# Sheet1.net
KiCad netlist of a schematic drawn in Altium Designer
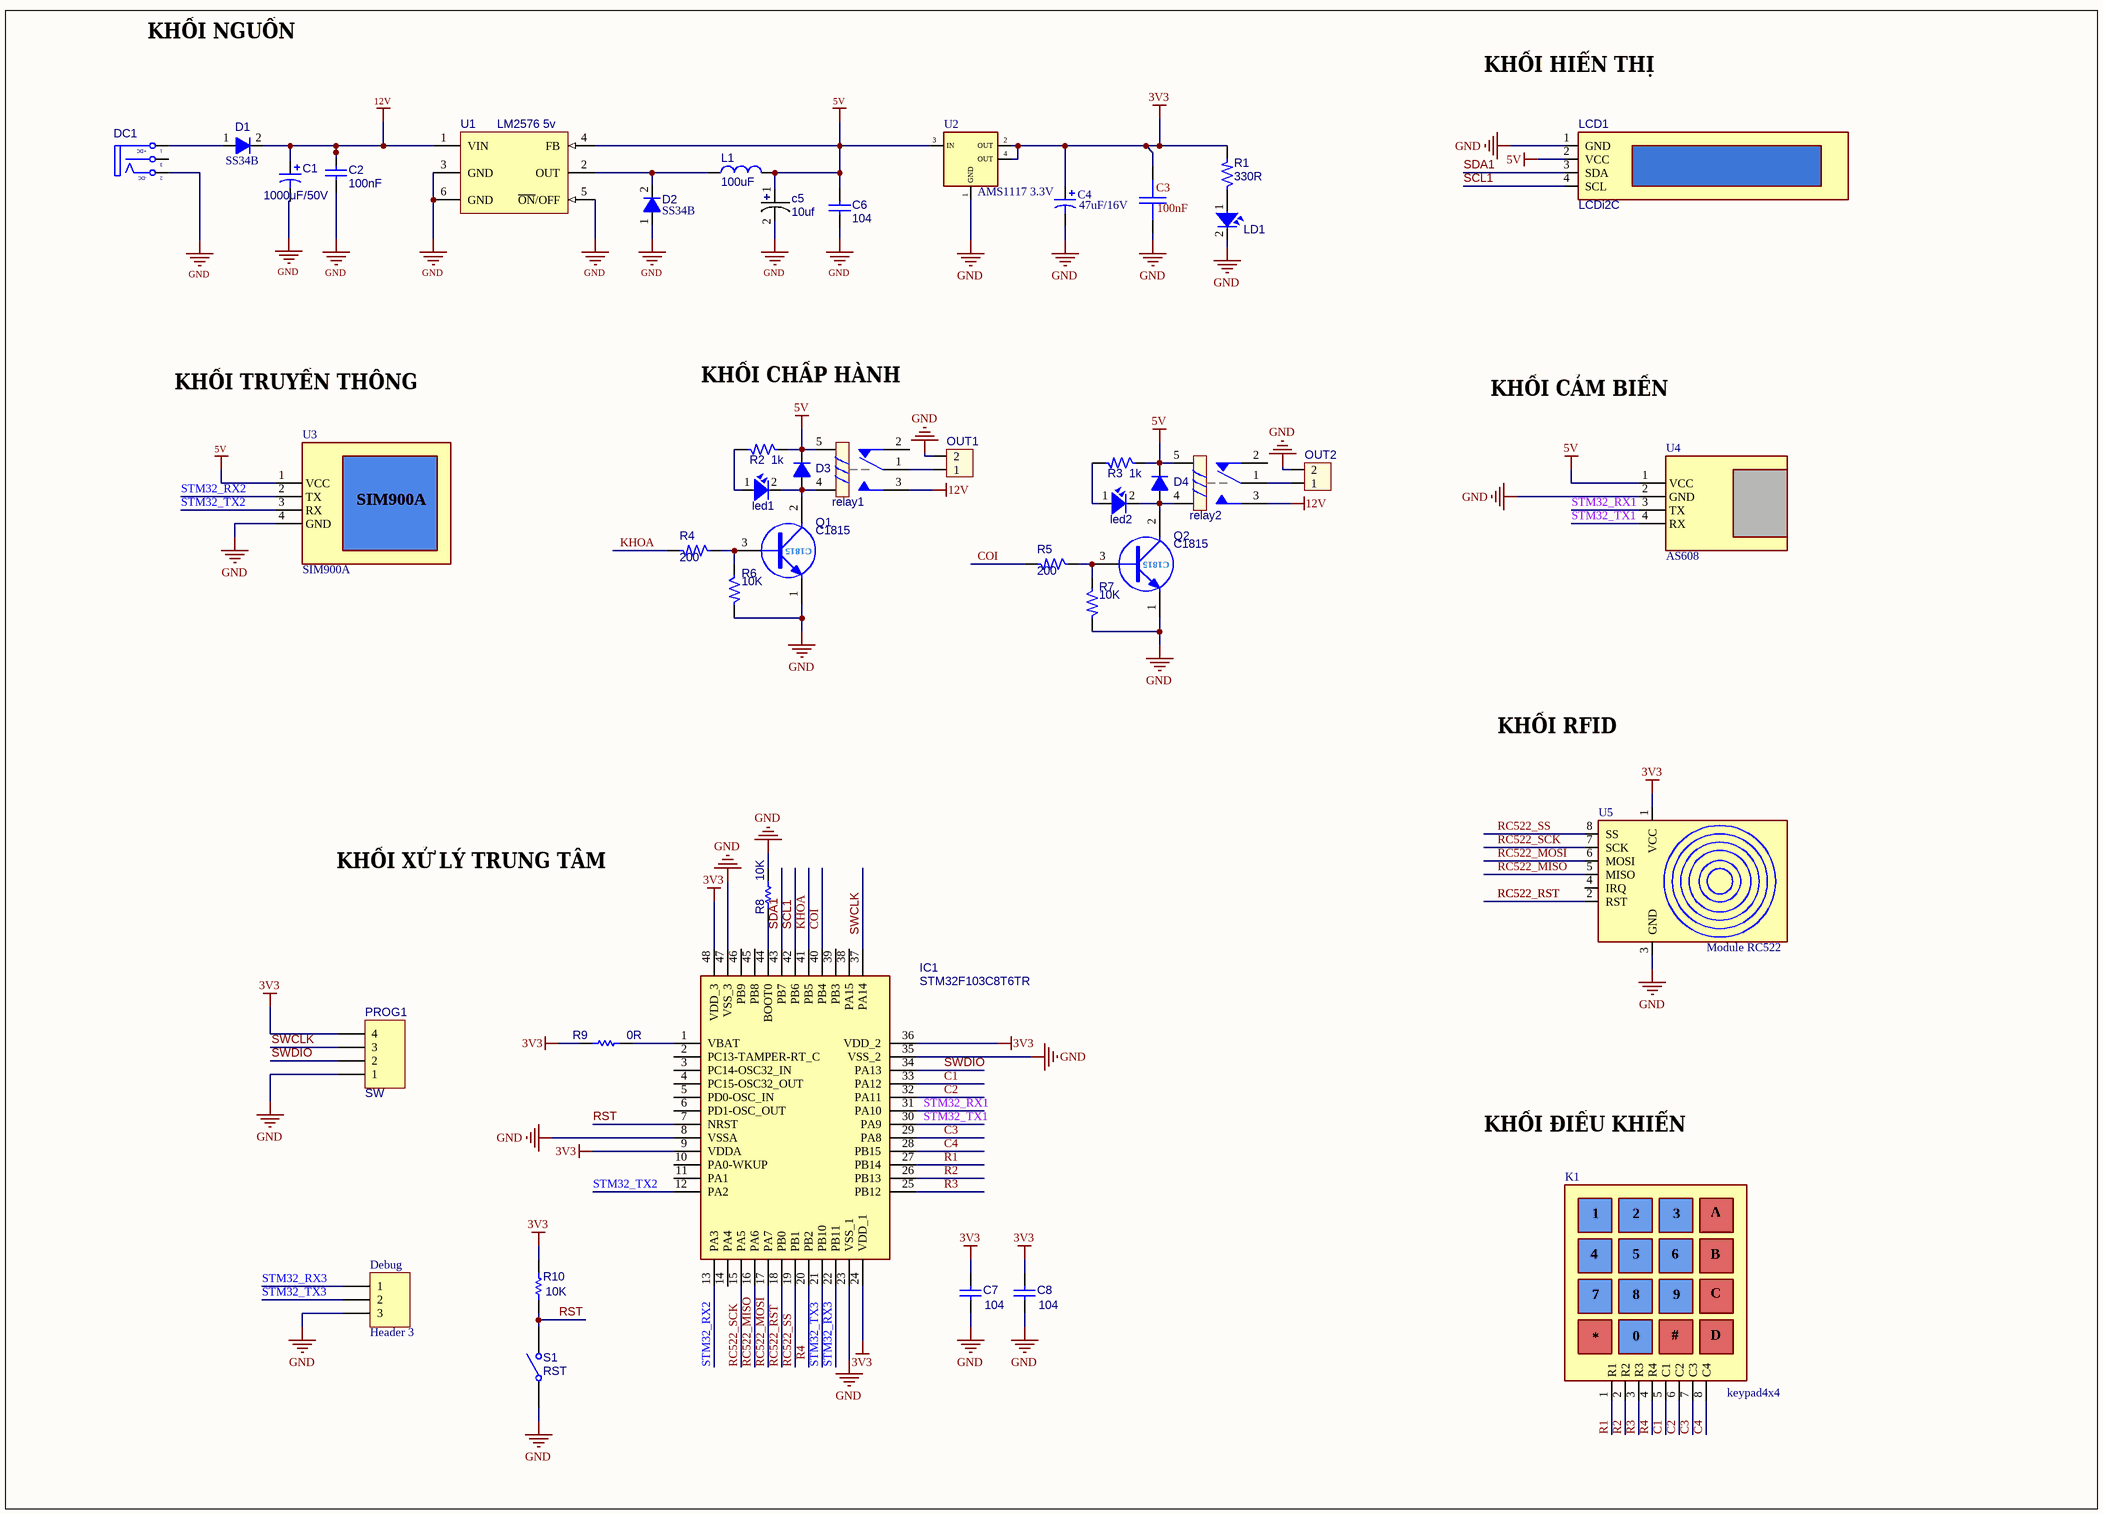
[diagram p0: Sheet1.SchDoc]

(export (version "E")
  (design (tool "Eeschema 10.0.6"))
  (components
    (comp (ref "C1")
      (value "1000uF/50V")
      (footprint "C_EL_10_12")
      (description "Polarized Capacitor (Radial)")
      (fields (field (name "Comment") "1000uF-50V-DIP") (field (name "PUBLISHER") "Altium Limited"))
      (libsource (lib "Miscellaneous Devices") (part "Cap Pol1"))
    )
    (comp (ref "C2")
      (value "100nF")
      (footprint "C0805S")
      (description "Capacitor")
      (fields (field (name "Comment") "100nF-50V-126") (field (name "PUBLISHER") "Altium Limited"))
      (libsource (lib "Miscellaneous Devices") (part "Cap"))
    )
    (comp (ref "C3")
      (value "100nF")
      (footprint "C0805S")
      (description "Capacitor, Ceramic Chip, 16V, X7R, 10%")
      (fields
        (field (name "MANUFACTURER") "Samsung Electromechanics")
        (field (name "PARTNUMBER") "CL05B104KO5NNNC")
      )
      (libsource (lib "PADSlegacy_Passive") (part "C0402"))
    )
    (comp (ref "C4")
      (value "47uF/16V")
      (footprint "6032")
      (description "Polarized Capacitor (Radial)")
      (fields (field (name "Comment") "Tanta-47uF-16V-2917") (field (name "PUBLISHER") "Altium Limited"))
      (libsource (lib "Miscellaneous Devices") (part "Cap Pol1"))
    )
    (comp (ref "c5")
      (value "10uf")
      (footprint "C_EL_10_9")
      (libsource (lib "Schlib_do_an_2019") (part "radial"))
    )
    (comp (ref "C6")
      (value "104")
      (footprint "C0805S")
      (description "Capacitor (Semiconductor SIM Model)")
      (fields (field (name "PUBLISHER") "Altium Limited"))
      (libsource (lib "Pcblib_do_an_2019") (part "Cap 104_SMD"))
    )
    (comp (ref "C7")
      (value "104")
      (footprint "C0805S")
      (description "Capacitor")
      (fields (field (name "Comment") "Cap") (field (name "PUBLISHER") "Altium Limited"))
      (libsource (lib "Miscellaneous Devices") (part "Cap"))
    )
    (comp (ref "C8")
      (value "104")
      (footprint "C0805S")
      (description "Capacitor")
      (fields (field (name "Comment") "Cap") (field (name "PUBLISHER") "Altium Limited"))
      (libsource (lib "Miscellaneous Devices") (part "Cap"))
    )
    (comp (ref "D1") (value "SS34B") (footprint "D_SMB") (libsource (lib "Schlib_do_an_2019") (part "diode")))
    (comp (ref "D2") (value "SS34B") (footprint "D_SMB") (libsource (lib "Schlib_do_an_2019") (part "diode")))
    (comp (ref "D3") (value "diode") (footprint "D_SMA") (libsource (lib "Pcblib_do_an_2019") (part "diode")))
    (comp (ref "D4") (value "diode") (footprint "D_SMA") (libsource (lib "Pcblib_do_an_2019") (part "diode")))
    (comp (ref "DC1")
      (value "Jack DC5.5x2.5MM DC5525")
      (footprint "DC-IN")
      (description "Jac DC input")
      (libsource (lib "syhaunguyen") (part "DCIN"))
    )
    (comp (ref "Debug")
      (value "Header 3")
      (footprint "XH_3")
      (description "Header, 3-Pin")
      (fields (field (name "PUBLISHER") "Altium Limited"))
      (libsource (lib "Miscellaneous Connectors") (part "Header 3"))
    )
    (comp (ref "IC1")
      (value "STM32F103C8T6TR")
      (footprint "QFN48N")
      (description "Integrated Circuit")
      (fields (field (name "MOUSER PART NUMBER") "511-STM32F103C8T6TR"))
      (libsource (lib "*") (part "STM32F103C8T6TR"))
    )
    (comp (ref "K1") (value "keypad4x4") (footprint "XH_8") (libsource (lib "kctm_lib") (part "keypad")))
    (comp (ref "L1")
      (value "100uF")
      (footprint "L_12")
      (description "Inductor")
      (libsource (lib "Lib_Chuan_03_08_2013") (part "L1"))
    )
    (comp (ref "LCD1") (value "LCDi2C") (footprint "XH_4") (libsource (lib "lib_vuon_dua") (part "LCDi2C")))
    (comp (ref "LD1")
      (value "led 0805 green")
      (footprint "LED0805GRN")
      (libsource (lib "Schlib_do_an_2019") (part "led"))
    )
    (comp (ref "led1")
      (value "led")
      (footprint "led 5mm red dip")
      (libsource (lib "Schlib_do_an_2019") (part "led"))
    )
    (comp (ref "led2")
      (value "led")
      (footprint "led 5mm red dip")
      (libsource (lib "Schlib_do_an_2019") (part "led"))
    )
    (comp (ref "OUT1")
      (value "con2")
      (footprint "MSTBF_2")
      (libsource (lib "Schlib_do_an_2019") (part "con2"))
    )
    (comp (ref "OUT2")
      (value "con2")
      (footprint "MSTBF_2")
      (libsource (lib "Schlib_do_an_2019") (part "con2"))
    )
    (comp (ref "PROG1")
      (value "SW")
      (footprint "XH_4")
      (description "Header, 4-Pin")
      (fields (field (name "PUBLISHER") "Altium Limited"))
      (libsource (lib "Miscellaneous Connectors") (part "Header 4"))
    )
    (comp (ref "Q1")
      (value "C1815")
      (footprint "VuNgocDang:TO-92W")
      (libsource (lib "Schlib_do_an_2019") (part "C1815"))
    )
    (comp (ref "Q2")
      (value "C1815")
      (footprint "VuNgocDang:TO-92W")
      (libsource (lib "Schlib_do_an_2019") (part "C1815"))
    )
    (comp (ref "R1")
      (value "330R")
      (footprint "R0805E")
      (description "Resistor 1/4W")
      (libsource (lib "library_2") (part "R"))
    )
    (comp (ref "R2")
      (value "1k")
      (footprint "R0805E")
      (description "Resistor 1/4W")
      (libsource (lib "Pcblib_do_an_2019") (part "R"))
    )
    (comp (ref "R3")
      (value "1k")
      (footprint "R0805E")
      (description "Resistor 1/4W")
      (libsource (lib "Pcblib_do_an_2019") (part "R"))
    )
    (comp (ref "R4")
      (value "200")
      (footprint "R0125W_AX03")
      (description "Resistor 1/4W")
      (libsource (lib "Pcblib_do_an_2019") (part "R"))
    )
    (comp (ref "R5")
      (value "200")
      (footprint "R0125W_AX03")
      (description "Resistor 1/4W")
      (libsource (lib "Pcblib_do_an_2019") (part "R"))
    )
    (comp (ref "R6")
      (value "10K")
      (footprint "R0805E")
      (description "Resistor 1/4W")
      (libsource (lib "Pcblib_do_an_2019") (part "R"))
    )
    (comp (ref "R7")
      (value "10K")
      (footprint "R0805E")
      (description "Resistor 1/4W")
      (libsource (lib "Pcblib_do_an_2019") (part "R"))
    )
    (comp (ref "R8")
      (value "10K")
      (footprint "SmartDoor:R0805E")
      (description "Resistor")
      (fields (field (name "Comment") "Res1") (field (name "PUBLISHER") "Altium Limited"))
      (libsource (lib "Miscellaneous Devices") (part "Res1"))
    )
    (comp (ref "R9")
      (value "0R")
      (footprint "R0805S")
      (description "Resistor")
      (fields (field (name "Comment") "Res1") (field (name "PUBLISHER") "Altium Limited"))
      (libsource (lib "Miscellaneous Devices") (part "Res1"))
    )
    (comp (ref "R10")
      (value "10K")
      (footprint "R0805S")
      (description "Resistor")
      (fields (field (name "Comment") "Res1") (field (name "PUBLISHER") "Altium Limited"))
      (libsource (lib "Miscellaneous Devices") (part "Res1"))
    )
    (comp (ref "relay1")
      (value "relay2")
      (footprint "RL_SPDT_10A")
      (libsource (lib "Schlib_do_an_2019") (part "relay2"))
    )
    (comp (ref "relay2")
      (value "relay2")
      (footprint "RL_SPDT_10A")
      (libsource (lib "Schlib_do_an_2019") (part "relay2"))
    )
    (comp (ref "S1")
      (value "RST")
      (footprint "SW1-SMD")
      (description "Single-Pole, Single-Throw Switch")
      (fields (field (name "PUBLISHER") "Altium Limited"))
      (libsource (lib "Miscellaneous Devices") (part "SW-SPST"))
    )
    (comp (ref "U1")
      (value "LM2576 5v")
      (footprint "TO-263-5L, D2PAK-5, DDPAK, FMG170_5_S1000")
      (description "SIMPLE SWITCHER; 3A Step-Down Voltage Regulator")
      (fields
        (field (name "PARTNUMBER") "LM2576T-5.0")
        (field (name "MANUFACTURER") "National Semiconductor")
        (field (name "PUBLISHER") "Altium Limited")
      )
      (libsource (lib "Lib_Chuan_03_08_2013") (part "LM2576T-5.0"))
    )
    (comp (ref "U2")
      (value "AMS1117 3.3V")
      (footprint "TranVanDen:ASM1117-3V3")
      (libsource (lib "HF6200_Lib") (part "AMS1117"))
    )
    (comp (ref "U3") (value "SIM900A") (footprint "XH_4") (libsource (lib "SmartDoor") (part "SIM900A")))
    (comp (ref "U4") (value "AS608") (footprint "XH_4") (libsource (lib "user_lib") (part "R307")))
    (comp (ref "U5")
      (value "Module RC522")
      (footprint "XH_8")
      (libsource (lib "QuanLyHangHoa_Lib") (part "Module RC522"))
    )
  )
  (nets
    (net (code "1") (name "/C1") (class "Default")
      (node (ref "IC1") (pin "33") (pinfunction "PA12_33") (pintype "passive"))
      (node (ref "K1") (pin "5") (pinfunction "C1_5") (pintype "passive"))
    )
    (net (code "2") (name "/C2") (class "Default")
      (node (ref "IC1") (pin "32") (pinfunction "PA11_32") (pintype "passive"))
      (node (ref "K1") (pin "6") (pinfunction "C2_6") (pintype "passive"))
    )
    (net (code "3") (name "/C3") (class "Default")
      (node (ref "IC1") (pin "29") (pinfunction "PA8_29") (pintype "passive"))
      (node (ref "K1") (pin "7") (pinfunction "C3_7") (pintype "passive"))
    )
    (net (code "4") (name "/C4") (class "Default")
      (node (ref "IC1") (pin "28") (pinfunction "PB15_28") (pintype "passive"))
      (node (ref "K1") (pin "8") (pinfunction "C4_8") (pintype "passive"))
    )
    (net (code "5") (name "/COI") (class "Default")
      (node (ref "IC1") (pin "40") (pinfunction "PB4_40") (pintype "passive"))
      (node (ref "R5") (pin "2") (pinfunction "2_2") (pintype "passive"))
    )
    (net (code "6") (name "/KHOA") (class "Default")
      (node (ref "IC1") (pin "41") (pinfunction "PB5_41") (pintype "passive"))
      (node (ref "R4") (pin "2") (pinfunction "2_2") (pintype "passive"))
    )
    (net (code "7") (name "/R1") (class "Default")
      (node (ref "IC1") (pin "27") (pinfunction "PB14_27") (pintype "passive"))
      (node (ref "K1") (pin "1") (pinfunction "R1_1") (pintype "passive"))
    )
    (net (code "8") (name "/R2") (class "Default")
      (node (ref "IC1") (pin "26") (pinfunction "PB13_26") (pintype "passive"))
      (node (ref "K1") (pin "2") (pinfunction "R2_2") (pintype "passive"))
    )
    (net (code "9") (name "/R3") (class "Default")
      (node (ref "IC1") (pin "25") (pinfunction "PB12_25") (pintype "passive"))
      (node (ref "K1") (pin "3") (pinfunction "R3_3") (pintype "passive"))
    )
    (net (code "10") (name "/R4") (class "Default")
      (node (ref "IC1") (pin "20") (pinfunction "PB2_20") (pintype "passive"))
      (node (ref "K1") (pin "4") (pinfunction "R4_4") (pintype "passive"))
    )
    (net (code "11") (name "/RC522_MISO") (class "Default")
      (node (ref "IC1") (pin "16") (pinfunction "PA6_16") (pintype "passive"))
      (node (ref "U5") (pin "5") (pinfunction "MISO_5") (pintype "passive"))
    )
    (net (code "12") (name "/RC522_MOSI") (class "Default")
      (node (ref "IC1") (pin "17") (pinfunction "PA7_17") (pintype "passive"))
      (node (ref "U5") (pin "6") (pinfunction "MOSI_6") (pintype "passive"))
    )
    (net (code "13") (name "/RC522_RST") (class "Default")
      (node (ref "IC1") (pin "18") (pinfunction "PB0_18") (pintype "passive"))
      (node (ref "U5") (pin "2") (pinfunction "RST_2") (pintype "passive"))
    )
    (net (code "14") (name "/RC522_SCK") (class "Default")
      (node (ref "IC1") (pin "15") (pinfunction "PA5_15") (pintype "passive"))
      (node (ref "U5") (pin "7") (pinfunction "SCK_7") (pintype "passive"))
    )
    (net (code "15") (name "/RC522_SS") (class "Default")
      (node (ref "IC1") (pin "19") (pinfunction "PB1_19") (pintype "passive"))
      (node (ref "U5") (pin "8") (pinfunction "SS_8") (pintype "passive"))
    )
    (net (code "16") (name "/RST") (class "Default")
      (node (ref "IC1") (pin "7") (pinfunction "NRST_7") (pintype "passive"))
      (node (ref "R10") (pin "1") (pinfunction "1_1") (pintype "passive"))
      (node (ref "S1") (pin "2") (pinfunction "NO_2") (pintype "passive"))
    )
    (net (code "17") (name "/SCL1") (class "Default")
      (node (ref "IC1") (pin "42") (pinfunction "PB6_42") (pintype "passive"))
      (node (ref "LCD1") (pin "4") (pinfunction "SCL_4") (pintype "passive"))
    )
    (net (code "18") (name "/SDA1") (class "Default")
      (node (ref "IC1") (pin "43") (pinfunction "PB7_43") (pintype "passive"))
      (node (ref "LCD1") (pin "3") (pinfunction "SDA_3") (pintype "passive"))
    )
    (net (code "19") (name "/STM32_RX1") (class "Default")
      (node (ref "IC1") (pin "31") (pinfunction "PA10_31") (pintype "passive"))
      (node (ref "U4") (pin "3") (pinfunction "TX_3") (pintype "passive"))
    )
    (net (code "20") (name "/STM32_RX2") (class "Default")
      (node (ref "IC1") (pin "13") (pinfunction "PA3_13") (pintype "passive"))
      (node (ref "U3") (pin "2") (pinfunction "TX_2") (pintype "passive"))
    )
    (net (code "21") (name "/STM32_RX3") (class "Default")
      (node (ref "Debug") (pin "1") (pinfunction "1_1") (pintype "passive"))
      (node (ref "IC1") (pin "22") (pinfunction "PB11_22") (pintype "passive"))
    )
    (net (code "22") (name "/STM32_TX1") (class "Default")
      (node (ref "IC1") (pin "30") (pinfunction "PA9_30") (pintype "passive"))
      (node (ref "U4") (pin "4") (pinfunction "RX_4") (pintype "passive"))
    )
    (net (code "23") (name "/STM32_TX2") (class "Default")
      (node (ref "IC1") (pin "12") (pinfunction "PA2_12") (pintype "passive"))
      (node (ref "U3") (pin "3") (pinfunction "RX_3") (pintype "passive"))
    )
    (net (code "24") (name "/STM32_TX3") (class "Default")
      (node (ref "Debug") (pin "2") (pinfunction "2_2") (pintype "passive"))
      (node (ref "IC1") (pin "21") (pinfunction "PB10_21") (pintype "passive"))
    )
    (net (code "25") (name "/SWCLK") (class "Default")
      (node (ref "IC1") (pin "37") (pinfunction "PA14_37") (pintype "passive"))
      (node (ref "PROG1") (pin "3") (pinfunction "3_3") (pintype "passive"))
    )
    (net (code "26") (name "/SWDIO") (class "Default")
      (node (ref "IC1") (pin "34") (pinfunction "PA13_34") (pintype "passive"))
      (node (ref "PROG1") (pin "2") (pinfunction "2_2") (pintype "passive"))
    )
    (net (code "27") (name "3V3") (class "Default")
      (node (ref "C3") (pin "2") (pinfunction "2_2") (pintype "passive"))
      (node (ref "C4") (pin "1") (pinfunction "1_1") (pintype "passive"))
      (node (ref "C7") (pin "2") (pinfunction "2_2") (pintype "passive"))
      (node (ref "C8") (pin "2") (pinfunction "2_2") (pintype "passive"))
      (node (ref "IC1") (pin "24") (pinfunction "VDD_1_24") (pintype "passive"))
      (node (ref "IC1") (pin "36") (pinfunction "VDD_2_36") (pintype "passive"))
      (node (ref "IC1") (pin "48") (pinfunction "VDD_3_48") (pintype "passive"))
      (node (ref "IC1") (pin "9") (pinfunction "VDDA_9") (pintype "passive"))
      (node (ref "PROG1") (pin "4") (pinfunction "4_4") (pintype "passive"))
      (node (ref "R1") (pin "2") (pinfunction "2_2") (pintype "passive"))
      (node (ref "R10") (pin "2") (pinfunction "2_2") (pintype "passive"))
      (node (ref "R9") (pin "2") (pinfunction "2_2") (pintype "passive"))
      (node (ref "U2") (pin "2") (pinfunction "OUT_2") (pintype "passive"))
      (node (ref "U2") (pin "4") (pinfunction "OUT_4") (pintype "passive"))
      (node (ref "U5") (pin "1") (pinfunction "VCC_1") (pintype "passive"))
    )
    (net (code "28") (name "5V") (class "Default")
      (node (ref "C6") (pin "2") (pintype "passive"))
      (node (ref "D3") (pin "2") (pinfunction "K_2") (pintype "passive"))
      (node (ref "D4") (pin "2") (pinfunction "K_2") (pintype "passive"))
      (node (ref "L1") (pin "2") (pinfunction "2_2") (pintype "passive"))
      (node (ref "LCD1") (pin "2") (pinfunction "VCC_2") (pintype "passive"))
      (node (ref "R2") (pin "1") (pinfunction "1_1") (pintype "passive"))
      (node (ref "R3") (pin "1") (pinfunction "1_1") (pintype "passive"))
      (node (ref "U1") (pin "4") (pinfunction "FB_4") (pintype "input"))
      (node (ref "U2") (pin "3") (pinfunction "IN_3") (pintype "passive"))
      (node (ref "U3") (pin "1") (pinfunction "VCC_1") (pintype "passive"))
      (node (ref "U4") (pin "1") (pinfunction "VCC_1") (pintype "passive"))
      (node (ref "c5") (pin "1") (pinfunction "1_1") (pintype "passive"))
      (node (ref "relay1") (pin "5") (pinfunction "5_5") (pintype "passive"))
      (node (ref "relay2") (pin "5") (pinfunction "5_5") (pintype "passive"))
    )
    (net (code "29") (name "12V") (class "Default")
      (node (ref "C1") (pin "1") (pinfunction "1_1") (pintype "passive"))
      (node (ref "C2") (pin "1") (pinfunction "1_1") (pintype "passive"))
      (node (ref "D1") (pin "2") (pinfunction "K_2") (pintype "passive"))
      (node (ref "U1") (pin "1") (pinfunction "VIN_1") (pintype "power_in"))
      (node (ref "relay1") (pin "3") (pinfunction "3_3") (pintype "passive"))
      (node (ref "relay2") (pin "3") (pinfunction "3_3") (pintype "passive"))
    )
    (net (code "30") (name "GND") (class "Default")
      (node (ref "C1") (pin "2") (pinfunction "2_2") (pintype "passive"))
      (node (ref "C2") (pin "2") (pinfunction "2_2") (pintype "passive"))
      (node (ref "C3") (pin "1") (pinfunction "1_1") (pintype "passive"))
      (node (ref "C4") (pin "2") (pinfunction "2_2") (pintype "passive"))
      (node (ref "C6") (pin "1") (pintype "passive"))
      (node (ref "C7") (pin "1") (pinfunction "1_1") (pintype "passive"))
      (node (ref "C8") (pin "1") (pinfunction "1_1") (pintype "passive"))
      (node (ref "D2") (pin "1") (pinfunction "A_1") (pintype "passive"))
      (node (ref "DC1") (pin "2") (pinfunction "TN_2") (pintype "passive"))
      (node (ref "Debug") (pin "3") (pinfunction "3_3") (pintype "passive"))
      (node (ref "IC1") (pin "23") (pinfunction "VSS_1_23") (pintype "passive"))
      (node (ref "IC1") (pin "35") (pinfunction "VSS_2_35") (pintype "passive"))
      (node (ref "IC1") (pin "47") (pinfunction "VSS_3_47") (pintype "passive"))
      (node (ref "IC1") (pin "8") (pinfunction "VSSA_8") (pintype "passive"))
      (node (ref "LCD1") (pin "1") (pinfunction "GND_1") (pintype "passive"))
      (node (ref "LD1") (pin "2") (pinfunction "1_2") (pintype "passive"))
      (node (ref "OUT1") (pin "2") (pinfunction "2_2") (pintype "passive"))
      (node (ref "OUT2") (pin "2") (pinfunction "2_2") (pintype "passive"))
      (node (ref "PROG1") (pin "1") (pinfunction "1_1") (pintype "passive"))
      (node (ref "Q1") (pin "1") (pinfunction "E_1") (pintype "passive"))
      (node (ref "Q2") (pin "1") (pinfunction "E_1") (pintype "passive"))
      (node (ref "R6") (pin "2") (pinfunction "2_2") (pintype "passive"))
      (node (ref "R7") (pin "2") (pinfunction "2_2") (pintype "passive"))
      (node (ref "R8") (pin "1") (pinfunction "1_1") (pintype "passive"))
      (node (ref "S1") (pin "1") (pinfunction "COMMON_1") (pintype "passive"))
      (node (ref "U1") (pin "3") (pinfunction "GND_3") (pintype "power_in"))
      (node (ref "U1") (pin "5") (pinfunction "~{ON}/OFF_5") (pintype "input"))
      (node (ref "U1") (pin "6") (pinfunction "GND_6") (pintype "passive"))
      (node (ref "U2") (pin "1") (pinfunction "GND_1") (pintype "passive"))
      (node (ref "U3") (pin "4") (pinfunction "GND_4") (pintype "passive"))
      (node (ref "U4") (pin "2") (pinfunction "GND_2") (pintype "passive"))
      (node (ref "U5") (pin "3") (pinfunction "GND_3") (pintype "passive"))
      (node (ref "c5") (pin "2") (pinfunction "2_2") (pintype "passive"))
    )
    (net (code "31") (name "Net-(D1-A)") (class "Default")
      (node (ref "D1") (pin "1") (pinfunction "A_1") (pintype "passive"))
      (node (ref "DC1") (pin "1") (pinfunction "T_1") (pintype "passive"))
    )
    (net (code "32") (name "Net-(D2-K)") (class "Default")
      (node (ref "D2") (pin "2") (pinfunction "K_2") (pintype "passive"))
      (node (ref "L1") (pin "1") (pinfunction "1_1") (pintype "passive"))
      (node (ref "U1") (pin "2") (pinfunction "OUT_2") (pintype "power_in"))
    )
    (net (code "33") (name "Net-(D3-A)") (class "Default")
      (node (ref "D3") (pin "1") (pinfunction "A_1") (pintype "passive"))
      (node (ref "Q1") (pin "2") (pinfunction "C_2") (pintype "passive"))
      (node (ref "led1") (pin "2") (pinfunction "1_2") (pintype "passive"))
      (node (ref "relay1") (pin "4") (pinfunction "4_4") (pintype "passive"))
    )
    (net (code "34") (name "Net-(D4-A)") (class "Default")
      (node (ref "D4") (pin "1") (pinfunction "A_1") (pintype "passive"))
      (node (ref "Q2") (pin "2") (pinfunction "C_2") (pintype "passive"))
      (node (ref "led2") (pin "2") (pinfunction "1_2") (pintype "passive"))
      (node (ref "relay2") (pin "4") (pinfunction "4_4") (pintype "passive"))
    )
    (net (code "35") (name "Net-(IC1-BOOT0)") (class "Default")
      (node (ref "IC1") (pin "44") (pinfunction "BOOT0_44") (pintype "passive"))
      (node (ref "R8") (pin "2") (pinfunction "2_2") (pintype "passive"))
    )
    (net (code "36") (name "Net-(IC1-VBAT)") (class "Default")
      (node (ref "IC1") (pin "1") (pinfunction "VBAT_1") (pintype "passive"))
      (node (ref "R9") (pin "1") (pinfunction "1_1") (pintype "passive"))
    )
    (net (code "37") (name "Net-(LD1-A)") (class "Default")
      (node (ref "LD1") (pin "1") (pinfunction "A_1") (pintype "passive"))
      (node (ref "R1") (pin "1") (pinfunction "1_1") (pintype "passive"))
    )
    (net (code "38") (name "Net-(OUT1-Pad1)") (class "Default")
      (node (ref "OUT1") (pin "1") (pinfunction "1_1") (pintype "passive"))
      (node (ref "relay1") (pin "1") (pinfunction "1_1") (pintype "passive"))
    )
    (net (code "39") (name "Net-(OUT2-Pad1)") (class "Default")
      (node (ref "OUT2") (pin "1") (pinfunction "1_1") (pintype "passive"))
      (node (ref "relay2") (pin "1") (pinfunction "1_1") (pintype "passive"))
    )
    (net (code "40") (name "Net-(Q1-B)") (class "Default")
      (node (ref "Q1") (pin "3") (pinfunction "B_3") (pintype "passive"))
      (node (ref "R4") (pin "1") (pinfunction "1_1") (pintype "passive"))
      (node (ref "R6") (pin "1") (pinfunction "1_1") (pintype "passive"))
    )
    (net (code "41") (name "Net-(Q2-B)") (class "Default")
      (node (ref "Q2") (pin "3") (pinfunction "B_3") (pintype "passive"))
      (node (ref "R5") (pin "1") (pinfunction "1_1") (pintype "passive"))
      (node (ref "R7") (pin "1") (pinfunction "1_1") (pintype "passive"))
    )
    (net (code "42") (name "Net-(led1-A)") (class "Default")
      (node (ref "R2") (pin "2") (pinfunction "2_2") (pintype "passive"))
      (node (ref "led1") (pin "1") (pinfunction "A_1") (pintype "passive"))
    )
    (net (code "43") (name "Net-(led2-A)") (class "Default")
      (node (ref "R3") (pin "2") (pinfunction "2_2") (pintype "passive"))
      (node (ref "led2") (pin "1") (pinfunction "A_1") (pintype "passive"))
    )
    (net (code "44") (name "unconnected-(DC1-S-Pad3)") (class "Default")
      (node (ref "DC1") (pin "3") (pinfunction "S_3") (pintype "power_in"))
    )
    (net (code "45") (name "unconnected-(IC1-PA0-WKUP-Pad10)") (class "Default")
      (node (ref "IC1") (pin "10") (pinfunction "PA0-WKUP_10") (pintype "passive"))
    )
    (net (code "46") (name "unconnected-(IC1-PA1-Pad11)") (class "Default")
      (node (ref "IC1") (pin "11") (pinfunction "PA1_11") (pintype "passive"))
    )
    (net (code "47") (name "unconnected-(IC1-PA4-Pad14)") (class "Default")
      (node (ref "IC1") (pin "14") (pinfunction "PA4_14") (pintype "passive"))
    )
    (net (code "48") (name "unconnected-(IC1-PA15-Pad38)") (class "Default")
      (node (ref "IC1") (pin "38") (pinfunction "PA15_38") (pintype "passive"))
    )
    (net (code "49") (name "unconnected-(IC1-PB3-Pad39)") (class "Default")
      (node (ref "IC1") (pin "39") (pinfunction "PB3_39") (pintype "passive"))
    )
    (net (code "50") (name "unconnected-(IC1-PB8-Pad45)") (class "Default")
      (node (ref "IC1") (pin "45") (pinfunction "PB8_45") (pintype "passive"))
    )
    (net (code "51") (name "unconnected-(IC1-PB9-Pad46)") (class "Default")
      (node (ref "IC1") (pin "46") (pinfunction "PB9_46") (pintype "passive"))
    )
    (net (code "52") (name "unconnected-(IC1-PC13-TAMPER-RT_C-Pad2)") (class "Default")
      (node (ref "IC1") (pin "2") (pinfunction "PC13-TAMPER-RT_C_2") (pintype "passive"))
    )
    (net (code "53") (name "unconnected-(IC1-PC14-OSC32_IN-Pad3)") (class "Default")
      (node (ref "IC1") (pin "3") (pinfunction "PC14-OSC32_IN_3") (pintype "passive"))
    )
    (net (code "54") (name "unconnected-(IC1-PC15-OSC32_OUT-Pad4)") (class "Default")
      (node (ref "IC1") (pin "4") (pinfunction "PC15-OSC32_OUT_4") (pintype "passive"))
    )
    (net (code "55") (name "unconnected-(IC1-PD0-OSC_IN-Pad5)") (class "Default")
      (node (ref "IC1") (pin "5") (pinfunction "PD0-OSC_IN_5") (pintype "passive"))
    )
    (net (code "56") (name "unconnected-(IC1-PD1-OSC_OUT-Pad6)") (class "Default")
      (node (ref "IC1") (pin "6") (pinfunction "PD1-OSC_OUT_6") (pintype "passive"))
    )
    (net (code "57") (name "unconnected-(U5-IRQ-Pad4)") (class "Default")
      (node (ref "U5") (pin "4") (pinfunction "IRQ_4") (pintype "passive"))
    )
    (net (code "58") (name "unconnected-(relay1-Pad2)") (class "Default")
      (node (ref "relay1") (pin "2") (pinfunction "2_2") (pintype "passive"))
    )
    (net (code "59") (name "unconnected-(relay2-Pad2)") (class "Default")
      (node (ref "relay2") (pin "2") (pinfunction "2_2") (pintype "passive"))
    )
  )
)
